# InputChannel.net
KiCad netlist of a schematic drawn in Altium Designer
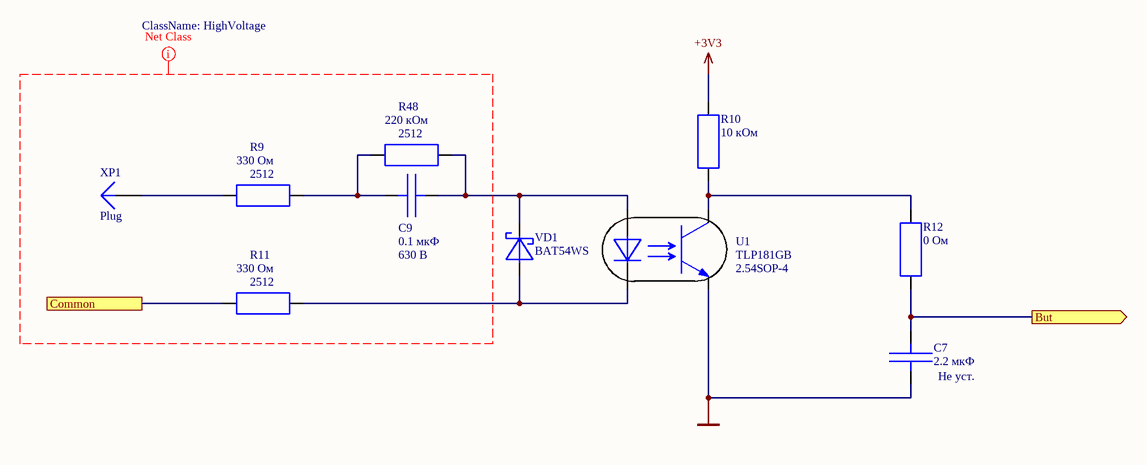
[diagram p0: InputChannel.SchDoc]

(export (version "E")
  (design (tool "Eeschema 10.0.6"))
  (components
    (comp (ref "C7")
      (value "Не уст.")
      (footprint "CAP_0603-1608")
      (description "Конденсатор")
      (fields (field (name "VOLTAGE") "6.3 В") (field (name "ALTIUM_VALUE") "2.2 мкФ"))
      (libsource (lib "GOST_Generic") (part "Cap"))
    )
    (comp (ref "C9")
      (value "0.1 мкФ")
      (footprint "CAP_1812-4532")
      (description "Конденсатор")
      (fields (field (name "VOLTAGE") "630 В") (field (name "Comment") "Cap"))
      (libsource (lib "GOST_Generic") (part "Cap"))
    )
    (comp (ref "R9")
      (value "330 Ом")
      (footprint "RES_2512-6332")
      (description "Резистор постоянный")
      (fields (field (name "CASE") "2512") (field (name "TOLERANCE") "5%") (field (name "Comment") "Res"))
      (libsource (lib "GOST_Generic") (part "Res"))
    )
    (comp (ref "R10")
      (value "10 кОм")
      (footprint "RES_0603-1608")
      (description "Резистор постоянный")
      (fields (field (name "TOLERANCE") "5%") (field (name "Comment") "Res"))
      (libsource (lib "GOST_Generic") (part "Res"))
    )
    (comp (ref "R11")
      (value "330 Ом")
      (footprint "RES_2512-6332")
      (description "Резистор постоянный")
      (fields (field (name "CASE") "2512") (field (name "TOLERANCE") "5%") (field (name "Comment") "Res"))
      (libsource (lib "GOST_Generic") (part "Res"))
    )
    (comp (ref "R12")
      (value "0 Ом")
      (footprint "RES_0603-1608")
      (description "Резистор постоянный")
      (fields (field (name "TOLERANCE") "5%") (field (name "Comment") "Res"))
      (libsource (lib "GOST_Generic") (part "Res"))
    )
    (comp (ref "R48")
      (value "220 кОм")
      (footprint "RES_2512-6332")
      (description "Резистор постоянный")
      (fields (field (name "CASE") "2512") (field (name "TOLERANCE") "5%") (field (name "Comment") "Res"))
      (libsource (lib "GOST_Generic") (part "Res"))
    )
    (comp (ref "U1")
      (value "OptoIso_Trans")
      (footprint "SOP-2.54-4")
      (description "Оптопара транзисторная")
      (fields (field (name "CASE") "2.54SOP-4") (field (name "TYPE") "TLP181GB"))
      (libsource (lib "GOST_Generic") (part "OptoIso_Trans"))
    )
    (comp (ref "VD1")
      (value "Diode_Schottky")
      (footprint "SOD-323")
      (description "Диод Шоттки")
      (fields (field (name "TYPE") "BAT54WS"))
      (libsource (lib "GOST_Generic") (part "Diode_Schottky"))
    )
    (comp (ref "XP1")
      (value "Plug")
      (footprint "EK508V_Pin")
      (fields (field (name "PUBLISHER") "Altium Limited"))
      (libsource (lib "Miscellaneous Connectors") (part "Plug"))
    )
  )
  (nets
    (net (code "1") (name "+3V3") (class "Default") (node (ref "R10") (pin "2") (pintype "passive")))
    (net (code "2") (name "/But") (class "Default")
      (node (ref "C7") (pin "2") (pinfunction "2_2") (pintype "passive"))
      (node (ref "R12") (pin "1") (pintype "passive"))
    )
    (net (code "3") (name "/Common") (class "Default") (node (ref "R11") (pin "1") (pintype "passive")))
    (net (code "4") (name "GND") (class "Default")
      (node (ref "C7") (pin "1") (pinfunction "1_1") (pintype "passive"))
      (node (ref "U1") (pin "3") (pinfunction "E_3") (pintype "passive"))
    )
    (net (code "5") (name "Net-(C9-Pad2)") (class "Default")
      (node (ref "C9") (pin "2") (pinfunction "2_2") (pintype "passive"))
      (node (ref "R48") (pin "1") (pintype "passive"))
      (node (ref "R9") (pin "2") (pintype "passive"))
    )
    (net (code "6") (name "Net-(R9-Pad1)") (class "Default")
      (node (ref "R9") (pin "1") (pintype "passive"))
      (node (ref "XP1") (pin "1") (pinfunction "1_1") (pintype "passive"))
    )
    (net (code "7") (name "Net-(U1-A)") (class "Default")
      (node (ref "C9") (pin "1") (pinfunction "1_1") (pintype "passive"))
      (node (ref "R48") (pin "2") (pintype "passive"))
      (node (ref "U1") (pin "1") (pinfunction "A_1") (pintype "passive"))
      (node (ref "VD1") (pin "2") (pinfunction "K_2") (pintype "passive"))
    )
    (net (code "8") (name "Net-(U1-C)") (class "Default")
      (node (ref "R10") (pin "1") (pintype "passive"))
      (node (ref "R12") (pin "2") (pintype "passive"))
      (node (ref "U1") (pin "4") (pinfunction "C_4") (pintype "passive"))
    )
    (net (code "9") (name "Net-(U1-K)") (class "Default")
      (node (ref "R11") (pin "2") (pintype "passive"))
      (node (ref "U1") (pin "2") (pinfunction "K_2") (pintype "passive"))
      (node (ref "VD1") (pin "1") (pinfunction "A_1") (pintype "passive"))
    )
  )
)
